# Magnetometers.net
KiCad netlist of a schematic drawn in Altium Designer
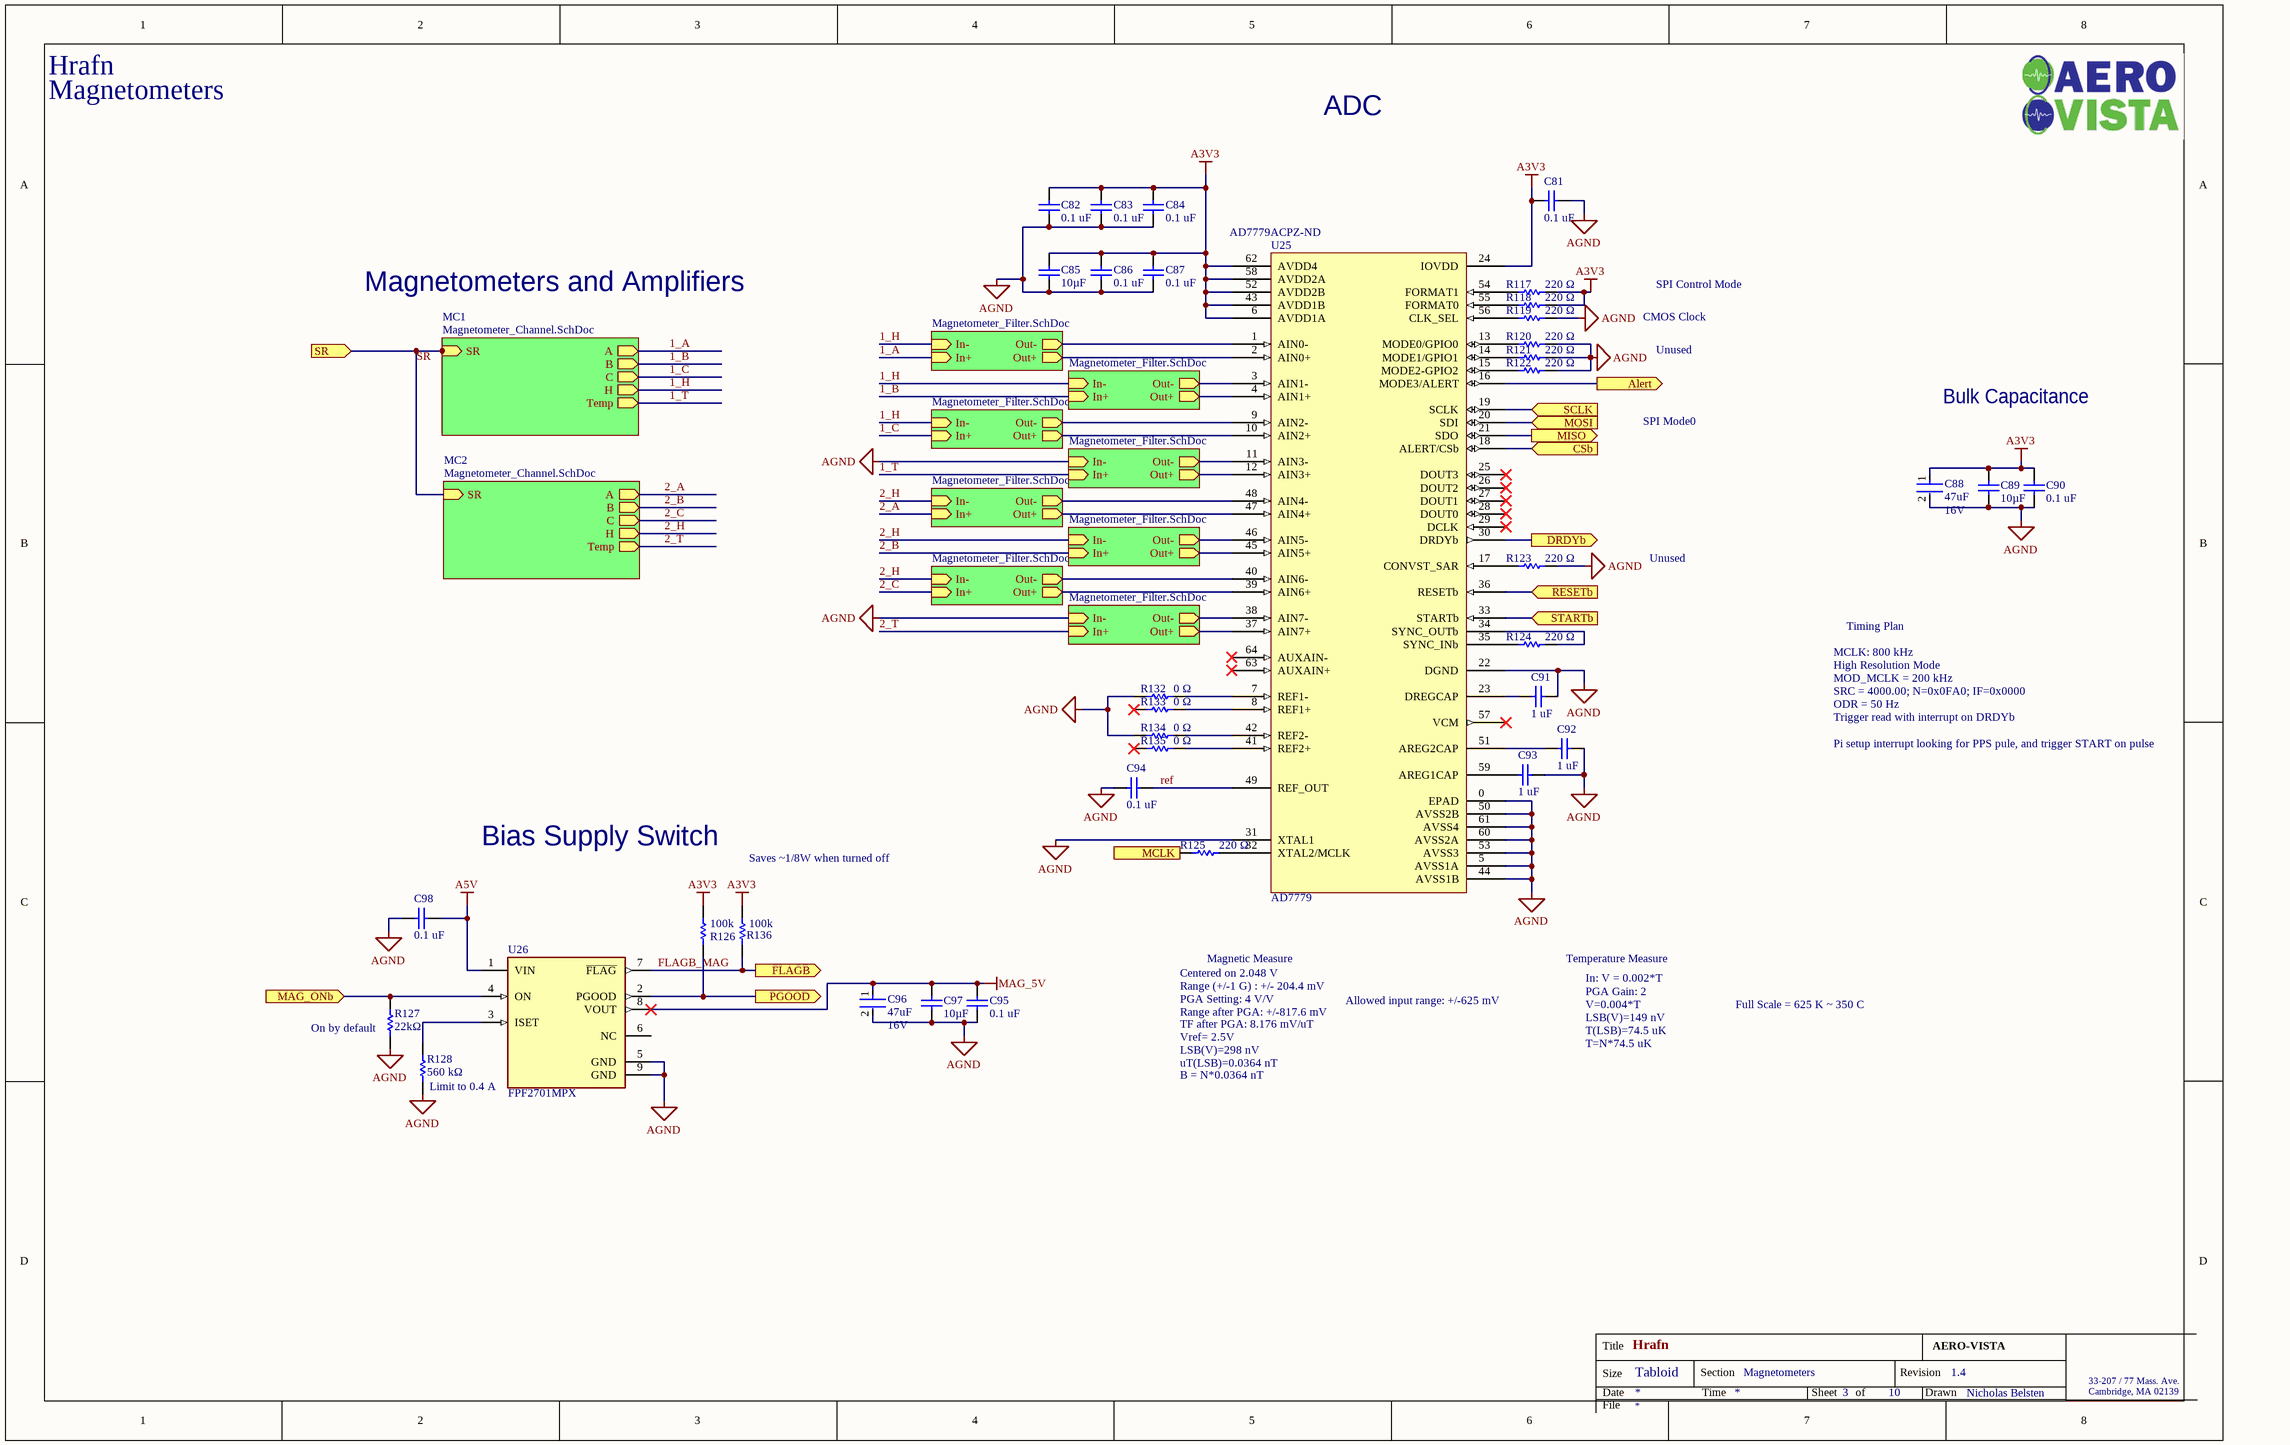
[diagram p0: Magnetometers.SchDoc]

(export (version "E")
  (design (tool "Eeschema 10.0.6"))
  (components
    (comp (ref "C81")
      (value "0.1 uF")
      (footprint "CAPC0402(1005)60_L")
      (description "CAP 100nF 16V ±5% 0402 (1005 Metric) Thickness 0.6mm SMD")
      (fields (field (name "TOLERANCE") "Â±5%"))
      (libsource (lib "Altium Content Vault") (part "CAP"))
    )
    (comp (ref "C82")
      (value "0.1 uF")
      (footprint "CAPC0402(1005)60_L")
      (description "CAP 100nF 16V ±5% 0402 (1005 Metric) Thickness 0.6mm SMD")
      (fields (field (name "TOLERANCE") "Â±5%"))
      (libsource (lib "Altium Content Vault") (part "CAP"))
    )
    (comp (ref "C83")
      (value "0.1 uF")
      (footprint "CAPC0402(1005)60_L")
      (description "CAP 100nF 16V ±5% 0402 (1005 Metric) Thickness 0.6mm SMD")
      (fields (field (name "TOLERANCE") "Â±5%"))
      (libsource (lib "Altium Content Vault") (part "CAP"))
    )
    (comp (ref "C84")
      (value "0.1 uF")
      (footprint "CAPC0402(1005)60_L")
      (description "CAP 100nF 16V ±5% 0402 (1005 Metric) Thickness 0.6mm SMD")
      (fields (field (name "TOLERANCE") "Â±5%"))
      (libsource (lib "Altium Content Vault") (part "CAP"))
    )
    (comp (ref "C85")
      (value "EMK107BBJ106MA-T")
      (footprint "CAPC1608X100X35LL20T25")
      (description "Chip Capacitor, 10 uF, +/- 20%, 16 V, -55 to 85 degC, 0603 (1608 Metric), RoHS, Tape and Reel")
      (fields
        (field (name "CAPACITANCE") "10µF")
        (field (name "MANUFACTURER") "Taiyo Yuden")
        (field (name "TOLERANCE") "±20%")
      )
      (libsource (lib "Altium Content Vault") (part "CAP-NP-2"))
    )
    (comp (ref "C86")
      (value "0.1 uF")
      (footprint "CAPC0402(1005)60_L")
      (description "CAP 100nF 16V ±5% 0402 (1005 Metric) Thickness 0.6mm SMD")
      (fields (field (name "TOLERANCE") "Â±5%"))
      (libsource (lib "Altium Content Vault") (part "CAP"))
    )
    (comp (ref "C87")
      (value "0.1 uF")
      (footprint "CAPC0402(1005)60_L")
      (description "CAP 100nF 16V ±5% 0402 (1005 Metric) Thickness 0.6mm SMD")
      (fields (field (name "TOLERANCE") "Â±5%"))
      (libsource (lib "Altium Content Vault") (part "CAP"))
    )
    (comp (ref "C88")
      (value "GRT32EC81C476ME13L")
      (footprint "FP-GRT32E-0_3-IPC_C")
      (description "Multi-Layer Ceramic Capacitor 47uF 16V X6S ±20% 1210 Emboss T/R")
      (fields
        (field (name "CAPACITANCE") "47uF")
        (field (name "VOLTAGE RATING") "16V")
        (field (name "TOLERANCE") "20%")
      )
      (libsource (lib "Altium Content Vault") (part "02cd4be3c70576c341d710602a673aa"))
    )
    (comp (ref "C89")
      (value "EMK107BBJ106MA-T")
      (footprint "CAPC1608X100X35LL20T25")
      (description "Chip Capacitor, 10 uF, +/- 20%, 16 V, -55 to 85 degC, 0603 (1608 Metric), RoHS, Tape and Reel")
      (fields
        (field (name "CAPACITANCE") "10µF")
        (field (name "MANUFACTURER") "Taiyo Yuden")
        (field (name "TOLERANCE") "±20%")
      )
      (libsource (lib "Altium Content Vault") (part "CAP-NP-2"))
    )
    (comp (ref "C90")
      (value "0.1 uF")
      (footprint "CAPC0402(1005)60_L")
      (description "CAP 100nF 16V ±5% 0402 (1005 Metric) Thickness 0.6mm SMD")
      (fields (field (name "TOLERANCE") "Â±5%"))
      (libsource (lib "Altium Content Vault") (part "CAP"))
    )
    (comp (ref "C91")
      (value "1 uF")
      (footprint "CAPC1005X60X30NL05T10")
      (fields (field (name "PART NUMBER") "C0402C105M8PACTU") (field (name "MANUFACTURER") "Kemet"))
      (libsource (lib "Altium Content Vault") (part "CAP"))
    )
    (comp (ref "C92")
      (value "1 uF")
      (footprint "CAPC1005X60X30NL05T10")
      (fields (field (name "PART NUMBER") "C0402C105M8PACTU") (field (name "MANUFACTURER") "Kemet"))
      (libsource (lib "Altium Content Vault") (part "CAP"))
    )
    (comp (ref "C93")
      (value "1 uF")
      (footprint "CAPC1005X60X30NL05T10")
      (fields (field (name "PART NUMBER") "C0402C105M8PACTU") (field (name "MANUFACTURER") "Kemet"))
      (libsource (lib "Altium Content Vault") (part "CAP"))
    )
    (comp (ref "C94")
      (value "0.1 uF")
      (footprint "CAPC0402(1005)60_L")
      (description "CAP 100nF 16V ±5% 0402 (1005 Metric) Thickness 0.6mm SMD")
      (fields (field (name "TOLERANCE") "Â±5%"))
      (libsource (lib "Altium Content Vault") (part "CAP"))
    )
    (comp (ref "C95")
      (value "0.1 uF")
      (footprint "CAPC0402(1005)60_L")
      (description "CAP 100nF 16V ±5% 0402 (1005 Metric) Thickness 0.6mm SMD")
      (fields (field (name "TOLERANCE") "Â±5%"))
      (libsource (lib "Altium Content Vault") (part "CAP"))
    )
    (comp (ref "C96")
      (value "GRT32EC81C476ME13L")
      (footprint "FP-GRT32E-0_3-IPC_C")
      (description "Multi-Layer Ceramic Capacitor 47uF 16V X6S ±20% 1210 Emboss T/R")
      (fields
        (field (name "CAPACITANCE") "47uF")
        (field (name "VOLTAGE RATING") "16V")
        (field (name "TOLERANCE") "20%")
      )
      (libsource (lib "Altium Content Vault") (part "02cd4be3c70576c341d710602a673aa"))
    )
    (comp (ref "C97")
      (value "EMK107BBJ106MA-T")
      (footprint "CAPC1608X100X35LL20T25")
      (description "Chip Capacitor, 10 uF, +/- 20%, 16 V, -55 to 85 degC, 0603 (1608 Metric), RoHS, Tape and Reel")
      (fields
        (field (name "CAPACITANCE") "10µF")
        (field (name "MANUFACTURER") "Taiyo Yuden")
        (field (name "TOLERANCE") "±20%")
      )
      (libsource (lib "Altium Content Vault") (part "CAP-NP-2"))
    )
    (comp (ref "C98")
      (value "0.1 uF")
      (footprint "CAPC0402(1005)60_L")
      (description "CAP 100nF 16V ±5% 0402 (1005 Metric) Thickness 0.6mm SMD")
      (fields (field (name "TOLERANCE") "Â±5%"))
      (libsource (lib "Altium Content Vault") (part "CAP"))
    )
    (comp (ref "R117")
      (value "220 Ω")
      (footprint "RESC1005X40X25LL05T05")
      (fields (field (name "PART NUMBER") "CRCW040220K0FKED") (field (name "MANUFACTURER") "Vishay Dale"))
      (libsource (lib "Altium Content Vault") (part "RES"))
    )
    (comp (ref "R118")
      (value "220 Ω")
      (footprint "RESC1005X40X25LL05T05")
      (fields (field (name "PART NUMBER") "CRCW040220K0FKED") (field (name "MANUFACTURER") "Vishay Dale"))
      (libsource (lib "Altium Content Vault") (part "RES"))
    )
    (comp (ref "R119")
      (value "220 Ω")
      (footprint "RESC1005X40X25LL05T05")
      (fields (field (name "PART NUMBER") "CRCW040220K0FKED") (field (name "MANUFACTURER") "Vishay Dale"))
      (libsource (lib "Altium Content Vault") (part "RES"))
    )
    (comp (ref "R120")
      (value "220 Ω")
      (footprint "RESC1005X40X25LL05T05")
      (fields (field (name "PART NUMBER") "CRCW040220K0FKED") (field (name "MANUFACTURER") "Vishay Dale"))
      (libsource (lib "Altium Content Vault") (part "RES"))
    )
    (comp (ref "R121")
      (value "220 Ω")
      (footprint "RESC1005X40X25LL05T05")
      (fields (field (name "PART NUMBER") "CRCW040220K0FKED") (field (name "MANUFACTURER") "Vishay Dale"))
      (libsource (lib "Altium Content Vault") (part "RES"))
    )
    (comp (ref "R122")
      (value "220 Ω")
      (footprint "RESC1005X40X25LL05T05")
      (fields (field (name "PART NUMBER") "CRCW040220K0FKED") (field (name "MANUFACTURER") "Vishay Dale"))
      (libsource (lib "Altium Content Vault") (part "RES"))
    )
    (comp (ref "R123")
      (value "220 Ω")
      (footprint "RESC1005X40X25NL05T05")
      (fields (field (name "PART NUMBER") "CRCW040220K0FKED") (field (name "MANUFACTURER") "Vishay Dale"))
      (libsource (lib "Altium Content Vault") (part "RES"))
    )
    (comp (ref "R124")
      (value "220 Ω")
      (footprint "RESC1005X40X25NL05T05")
      (fields (field (name "PART NUMBER") "CRCW040220K0FKED") (field (name "MANUFACTURER") "Vishay Dale"))
      (libsource (lib "Altium Content Vault") (part "RES"))
    )
    (comp (ref "R125")
      (value "220 Ω")
      (footprint "RESC1005X40X25LL05T05")
      (fields (field (name "PART NUMBER") "CRCW040220K0FKED") (field (name "MANUFACTURER") "Vishay Dale"))
      (libsource (lib "Altium Content Vault") (part "RES"))
    )
    (comp (ref "R126")
      (value "CRCW0402100KJNED")
      (footprint "RESC1005X40X25LL05T05")
      (fields (field (name "MANUFACTURER") "Vishay Dale") (field (name "RESISTANCE") "100k"))
      (libsource (lib "Altium Content Vault") (part "RES"))
    )
    (comp (ref "R127")
      (value "22kΩ")
      (footprint "RESC1005X40X25LL05T05")
      (fields (field (name "MANUFACTURER") "Panasonic") (field (name "PART NUMBER") "ERJ-2GEJ223X"))
      (libsource (lib "Altium Content Vault") (part "RES"))
    )
    (comp (ref "R128")
      (value "ERJ2RKF5603X")
      (footprint "RESC1005X40X25LL05T05")
      (fields (field (name "MANUFACTURER") "Panasonic") (field (name "RESISTANCE") "560 kΩ"))
      (libsource (lib "Altium Content Vault") (part "RES"))
    )
    (comp (ref "R132")
      (value "ERJ2GE0R00X")
      (footprint "RESC1005X40X25LL05T05")
      (description "Chip Resistor, 0 Ohm, 0.1 W, -55 to 155 degC, 0402 (1005 Metric), RoHS, Tape and Reel")
      (fields
        (field (name "MANUFACTURER") "Panasonic")
        (field (name "RESISTANCE") "0 Ω")
        (field (name "TOLERANCE") "5%")
      )
      (libsource (lib "Altium Content Vault") (part "RES-2"))
    )
    (comp (ref "R133")
      (value "ERJ2GE0R00X")
      (footprint "RESC1005X40X25LL05T05")
      (description "Chip Resistor, 0 Ohm, 0.1 W, -55 to 155 degC, 0402 (1005 Metric), RoHS, Tape and Reel")
      (fields
        (field (name "MANUFACTURER") "Panasonic")
        (field (name "RESISTANCE") "0 Ω")
        (field (name "TOLERANCE") "5%")
      )
      (libsource (lib "Altium Content Vault") (part "RES-2"))
    )
    (comp (ref "R134")
      (value "ERJ2GE0R00X")
      (footprint "RESC1005X40X25LL05T05")
      (description "Chip Resistor, 0 Ohm, 0.1 W, -55 to 155 degC, 0402 (1005 Metric), RoHS, Tape and Reel")
      (fields
        (field (name "MANUFACTURER") "Panasonic")
        (field (name "RESISTANCE") "0 Ω")
        (field (name "TOLERANCE") "5%")
      )
      (libsource (lib "Altium Content Vault") (part "RES-2"))
    )
    (comp (ref "R135")
      (value "ERJ2GE0R00X")
      (footprint "RESC1005X40X25LL05T05")
      (description "Chip Resistor, 0 Ohm, 0.1 W, -55 to 155 degC, 0402 (1005 Metric), RoHS, Tape and Reel")
      (fields
        (field (name "MANUFACTURER") "Panasonic")
        (field (name "RESISTANCE") "0 Ω")
        (field (name "TOLERANCE") "5%")
      )
      (libsource (lib "Altium Content Vault") (part "RES-2"))
    )
    (comp (ref "R136")
      (value "CRCW0402100KJNED")
      (footprint "RESC1005X40X25LL05T05")
      (fields (field (name "MANUFACTURER") "Vishay Dale") (field (name "RESISTANCE") "100k"))
      (libsource (lib "Altium Content Vault") (part "RES"))
    )
    (comp (ref "U25")
      (value "AD7779")
      (footprint "AD7779")
      (fields (field (name "SUPPLIER PART NUMBER 1") "AD7779ACPZ-ND"))
      (libsource (lib "Hrafn") (part "AD7779"))
    )
    (comp (ref "U26")
      (value "FPF2701MPX")
      (footprint "FP-511DD-MFG")
      (description "IC LOAD SWITCH 0.4-2A OCP 8MLP")
      (fields
        (field (name "OCTOPART") "https://octopart.com/fpf2701mpx-on+semiconductor-84327806")
        (field (name "MANUFACTURER") "ON Semiconductor")
      )
      (libsource (lib "Altium Content Vault") (part "acfcf82852ac67abfbd9dd99c9ad2d6"))
    )
  )
  (nets
    (net (code "11") (name "/Alert") (class "Default")
      (node (ref "U25") (pin "16") (pinfunction "MODE3/ALERT_16") (pintype "bidirectional"))
    )
    (net (code "12") (name "/CSb") (class "Default")
      (node (ref "U25") (pin "18") (pinfunction "ALERT/CSb_18") (pintype "bidirectional"))
    )
    (net (code "13") (name "/DRDYb") (class "Default")
      (node (ref "U25") (pin "30") (pinfunction "DRDYb_30") (pintype "output"))
    )
    (net (code "14") (name "/FLAGB_MAG") (class "Default")
      (node (ref "R136") (pin "1") (pinfunction "1_1") (pintype "passive"))
      (node (ref "U26") (pin "7") (pinfunction "~{FLAG}_7") (pintype "output"))
    )
    (net (code "15") (name "/MAG_ONb") (class "Default")
      (node (ref "R127") (pin "2") (pinfunction "2_2") (pintype "passive"))
      (node (ref "U26") (pin "4") (pinfunction "ON_4") (pintype "input"))
    )
    (net (code "16") (name "/MCLK") (class "Default")
      (node (ref "R125") (pin "1") (pinfunction "1_1") (pintype "passive"))
    )
    (net (code "17") (name "/MISO") (class "Default")
      (node (ref "U25") (pin "21") (pinfunction "SDO_21") (pintype "bidirectional"))
    )
    (net (code "18") (name "/MOSI") (class "Default")
      (node (ref "U25") (pin "20") (pinfunction "SDI_20") (pintype "bidirectional"))
    )
    (net (code "19") (name "/Out+") (class "Default")
      (node (ref "U25") (pin "37") (pinfunction "AIN7+_37") (pintype "input"))
    )
    (net (code "20") (name "/Out+_1") (class "Default")
      (node (ref "U25") (pin "4") (pinfunction "AIN1+_4") (pintype "input"))
    )
    (net (code "21") (name "/Out+_2") (class "Default")
      (node (ref "U25") (pin "2") (pinfunction "AIN0+_2") (pintype "input"))
    )
    (net (code "22") (name "/Out+_3") (class "Default")
      (node (ref "U25") (pin "10") (pinfunction "AIN2+_10") (pintype "input"))
    )
    (net (code "23") (name "/Out+_4") (class "Default")
      (node (ref "U25") (pin "47") (pinfunction "AIN4+_47") (pintype "input"))
    )
    (net (code "24") (name "/Out+_5") (class "Default")
      (node (ref "U25") (pin "12") (pinfunction "AIN3+_12") (pintype "input"))
    )
    (net (code "25") (name "/Out+_6") (class "Default")
      (node (ref "U25") (pin "39") (pinfunction "AIN6+_39") (pintype "input"))
    )
    (net (code "26") (name "/Out+_7") (class "Default")
      (node (ref "U25") (pin "45") (pinfunction "AIN5+_45") (pintype "input"))
    )
    (net (code "27") (name "/Out-") (class "Default")
      (node (ref "U25") (pin "38") (pinfunction "AIN7-_38") (pintype "input"))
    )
    (net (code "28") (name "/Out-_1") (class "Default")
      (node (ref "U25") (pin "1") (pinfunction "AIN0-_1") (pintype "input"))
    )
    (net (code "29") (name "/Out-_2") (class "Default")
      (node (ref "U25") (pin "3") (pinfunction "AIN1-_3") (pintype "input"))
    )
    (net (code "30") (name "/Out-_3") (class "Default")
      (node (ref "U25") (pin "9") (pinfunction "AIN2-_9") (pintype "input"))
    )
    (net (code "31") (name "/Out-_4") (class "Default")
      (node (ref "U25") (pin "48") (pinfunction "AIN4-_48") (pintype "input"))
    )
    (net (code "32") (name "/Out-_5") (class "Default")
      (node (ref "U25") (pin "11") (pinfunction "AIN3-_11") (pintype "input"))
    )
    (net (code "33") (name "/Out-_6") (class "Default")
      (node (ref "U25") (pin "46") (pinfunction "AIN5-_46") (pintype "input"))
    )
    (net (code "34") (name "/Out-_7") (class "Default")
      (node (ref "U25") (pin "40") (pinfunction "AIN6-_40") (pintype "input"))
    )
    (net (code "35") (name "/PGOOD") (class "Default")
      (node (ref "R126") (pin "1") (pinfunction "1_1") (pintype "passive"))
      (node (ref "U26") (pin "2") (pinfunction "PGOOD_2") (pintype "output"))
    )
    (net (code "36") (name "/RESETb") (class "Default")
      (node (ref "U25") (pin "36") (pinfunction "RESETb_36") (pintype "input"))
    )
    (net (code "37") (name "/SCLK") (class "Default")
      (node (ref "U25") (pin "19") (pinfunction "SCLK_19") (pintype "bidirectional"))
    )
    (net (code "39") (name "/STARTb") (class "Default")
      (node (ref "U25") (pin "33") (pinfunction "STARTb_33") (pintype "input"))
    )
    (net (code "40") (name "/ref") (class "Default")
      (node (ref "C94") (pin "2") (pinfunction "2_2") (pintype "passive"))
      (node (ref "U25") (pin "49") (pinfunction "REF_OUT_49") (pintype "passive"))
    )
    (net (code "41") (name "A3V3") (class "Default")
      (node (ref "C81") (pin "2") (pinfunction "2_2") (pintype "passive"))
      (node (ref "C82") (pin "2") (pinfunction "2_2") (pintype "passive"))
      (node (ref "C83") (pin "2") (pinfunction "2_2") (pintype "passive"))
      (node (ref "C84") (pin "2") (pinfunction "2_2") (pintype "passive"))
      (node (ref "C85") (pin "2") (pinfunction "2_2") (pintype "passive"))
      (node (ref "C86") (pin "2") (pinfunction "2_2") (pintype "passive"))
      (node (ref "C87") (pin "2") (pinfunction "2_2") (pintype "passive"))
      (node (ref "C88") (pin "1") (pinfunction "1_1") (pintype "passive"))
      (node (ref "C89") (pin "2") (pinfunction "2_2") (pintype "passive"))
      (node (ref "C90") (pin "2") (pinfunction "2_2") (pintype "passive"))
      (node (ref "R117") (pin "2") (pinfunction "2_2") (pintype "passive"))
      (node (ref "R118") (pin "2") (pinfunction "2_2") (pintype "passive"))
      (node (ref "R126") (pin "2") (pinfunction "2_2") (pintype "passive"))
      (node (ref "R136") (pin "2") (pinfunction "2_2") (pintype "passive"))
      (node (ref "U25") (pin "24") (pinfunction "IOVDD_24") (pintype "power_in"))
      (node (ref "U25") (pin "43") (pinfunction "AVDD1B_43") (pintype "power_in"))
      (node (ref "U25") (pin "52") (pinfunction "AVDD2B_52") (pintype "power_in"))
      (node (ref "U25") (pin "58") (pinfunction "AVDD2A_58") (pintype "power_in"))
      (node (ref "U25") (pin "6") (pinfunction "AVDD1A_6") (pintype "power_in"))
      (node (ref "U25") (pin "62") (pinfunction "AVDD4_62") (pintype "power_in"))
    )
    (net (code "42") (name "A5V") (class "Default")
      (node (ref "C98") (pin "2") (pinfunction "2_2") (pintype "passive"))
      (node (ref "U26") (pin "1") (pinfunction "VIN_1") (pintype "power_in"))
    )
    (net (code "43") (name "AGND") (class "Default")
      (node (ref "C81") (pin "1") (pinfunction "1_1") (pintype "passive"))
      (node (ref "C82") (pin "1") (pinfunction "1_1") (pintype "passive"))
      (node (ref "C83") (pin "1") (pinfunction "1_1") (pintype "passive"))
      (node (ref "C84") (pin "1") (pinfunction "1_1") (pintype "passive"))
      (node (ref "C85") (pin "1") (pinfunction "1_1") (pintype "passive"))
      (node (ref "C86") (pin "1") (pinfunction "1_1") (pintype "passive"))
      (node (ref "C87") (pin "1") (pinfunction "1_1") (pintype "passive"))
      (node (ref "C88") (pin "2") (pinfunction "2_2") (pintype "passive"))
      (node (ref "C89") (pin "1") (pinfunction "1_1") (pintype "passive"))
      (node (ref "C90") (pin "1") (pinfunction "1_1") (pintype "passive"))
      (node (ref "C91") (pin "1") (pinfunction "1_1") (pintype "passive"))
      (node (ref "C92") (pin "1") (pinfunction "1_1") (pintype "passive"))
      (node (ref "C93") (pin "1") (pinfunction "1_1") (pintype "passive"))
      (node (ref "C94") (pin "1") (pinfunction "1_1") (pintype "passive"))
      (node (ref "C95") (pin "1") (pinfunction "1_1") (pintype "passive"))
      (node (ref "C96") (pin "2") (pinfunction "2_2") (pintype "passive"))
      (node (ref "C97") (pin "1") (pinfunction "1_1") (pintype "passive"))
      (node (ref "C98") (pin "1") (pinfunction "1_1") (pintype "passive"))
      (node (ref "R119") (pin "2") (pinfunction "2_2") (pintype "passive"))
      (node (ref "R120") (pin "2") (pinfunction "2_2") (pintype "passive"))
      (node (ref "R121") (pin "2") (pinfunction "2_2") (pintype "passive"))
      (node (ref "R122") (pin "2") (pinfunction "2_2") (pintype "passive"))
      (node (ref "R123") (pin "2") (pinfunction "2_2") (pintype "passive"))
      (node (ref "R127") (pin "1") (pinfunction "1_1") (pintype "passive"))
      (node (ref "R128") (pin "1") (pinfunction "1_1") (pintype "passive"))
      (node (ref "R132") (pin "1") (pinfunction "1_1") (pintype "passive"))
      (node (ref "R134") (pin "1") (pinfunction "1_1") (pintype "passive"))
      (node (ref "U25") (pin "0") (pinfunction "EPAD_0") (pintype "power_in"))
      (node (ref "U25") (pin "22") (pinfunction "DGND_22") (pintype "power_in"))
      (node (ref "U25") (pin "31") (pinfunction "XTAL1_31") (pintype "passive"))
      (node (ref "U25") (pin "44") (pinfunction "AVSS1B_44") (pintype "power_in"))
      (node (ref "U25") (pin "5") (pinfunction "AVSS1A_5") (pintype "power_in"))
      (node (ref "U25") (pin "50") (pinfunction "AVSS2B_50") (pintype "power_in"))
      (node (ref "U25") (pin "53") (pinfunction "AVSS3_53") (pintype "power_in"))
      (node (ref "U25") (pin "60") (pinfunction "AVSS2A_60") (pintype "power_in"))
      (node (ref "U25") (pin "61") (pinfunction "AVSS4_61") (pintype "power_in"))
      (node (ref "U26") (pin "5") (pinfunction "GND_5") (pintype "power_in"))
      (node (ref "U26") (pin "9") (pinfunction "GND_9") (pintype "power_in"))
    )
    (net (code "44") (name "MAG_5V") (class "Default")
      (node (ref "C95") (pin "2") (pinfunction "2_2") (pintype "passive"))
      (node (ref "C96") (pin "1") (pinfunction "1_1") (pintype "passive"))
      (node (ref "C97") (pin "2") (pinfunction "2_2") (pintype "passive"))
      (node (ref "U26") (pin "8") (pinfunction "VOUT_8") (pintype "output"))
    )
    (net (code "45") (name "Net-(U25-AREG1CAP)") (class "Default")
      (node (ref "C93") (pin "2") (pinfunction "2_2") (pintype "passive"))
      (node (ref "U25") (pin "59") (pinfunction "AREG1CAP_59") (pintype "passive"))
    )
    (net (code "46") (name "Net-(U25-AREG2CAP)") (class "Default")
      (node (ref "C92") (pin "2") (pinfunction "2_2") (pintype "passive"))
      (node (ref "U25") (pin "51") (pinfunction "AREG2CAP_51") (pintype "passive"))
    )
    (net (code "47") (name "Net-(U25-CLK_SEL)") (class "Default")
      (node (ref "R119") (pin "1") (pinfunction "1_1") (pintype "passive"))
      (node (ref "U25") (pin "56") (pinfunction "CLK_SEL_56") (pintype "input"))
    )
    (net (code "48") (name "Net-(U25-CONVST_SAR)") (class "Default")
      (node (ref "R123") (pin "1") (pinfunction "1_1") (pintype "passive"))
      (node (ref "U25") (pin "17") (pinfunction "CONVST_SAR_17") (pintype "input"))
    )
    (net (code "49") (name "Net-(U25-DREGCAP)") (class "Default")
      (node (ref "C91") (pin "2") (pinfunction "2_2") (pintype "passive"))
      (node (ref "U25") (pin "23") (pinfunction "DREGCAP_23") (pintype "passive"))
    )
    (net (code "50") (name "Net-(U25-FORMAT0)") (class "Default")
      (node (ref "R118") (pin "1") (pinfunction "1_1") (pintype "passive"))
      (node (ref "U25") (pin "55") (pinfunction "FORMAT0_55") (pintype "input"))
    )
    (net (code "51") (name "Net-(U25-FORMAT1)") (class "Default")
      (node (ref "R117") (pin "1") (pinfunction "1_1") (pintype "passive"))
      (node (ref "U25") (pin "54") (pinfunction "FORMAT1_54") (pintype "input"))
    )
    (net (code "52") (name "Net-(U25-MODE0{slash}GPIO0)") (class "Default")
      (node (ref "R120") (pin "1") (pinfunction "1_1") (pintype "passive"))
      (node (ref "U25") (pin "13") (pinfunction "MODE0/GPIO0_13") (pintype "bidirectional"))
    )
    (net (code "53") (name "Net-(U25-MODE1{slash}GPIO1)") (class "Default")
      (node (ref "R121") (pin "1") (pinfunction "1_1") (pintype "passive"))
      (node (ref "U25") (pin "14") (pinfunction "MODE1/GPIO1_14") (pintype "bidirectional"))
    )
    (net (code "54") (name "Net-(U25-MODE2-GPIO2)") (class "Default")
      (node (ref "R122") (pin "1") (pinfunction "1_1") (pintype "passive"))
      (node (ref "U25") (pin "15") (pinfunction "MODE2-GPIO2_15") (pintype "bidirectional"))
    )
    (net (code "55") (name "Net-(U25-REF1+)") (class "Default")
      (node (ref "R133") (pin "2") (pinfunction "2_2") (pintype "passive"))
      (node (ref "U25") (pin "8") (pinfunction "REF1+_8") (pintype "input"))
    )
    (net (code "56") (name "Net-(U25-REF1-)") (class "Default")
      (node (ref "R132") (pin "2") (pinfunction "2_2") (pintype "passive"))
      (node (ref "U25") (pin "7") (pinfunction "REF1-_7") (pintype "input"))
    )
    (net (code "57") (name "Net-(U25-REF2+)") (class "Default")
      (node (ref "R135") (pin "2") (pinfunction "2_2") (pintype "passive"))
      (node (ref "U25") (pin "41") (pinfunction "REF2+_41") (pintype "input"))
    )
    (net (code "58") (name "Net-(U25-REF2-)") (class "Default")
      (node (ref "R134") (pin "2") (pinfunction "2_2") (pintype "passive"))
      (node (ref "U25") (pin "42") (pinfunction "REF2-_42") (pintype "input"))
    )
    (net (code "59") (name "Net-(U25-SYNC_INb)") (class "Default")
      (node (ref "R124") (pin "1") (pinfunction "1_1") (pintype "passive"))
      (node (ref "U25") (pin "35") (pinfunction "SYNC_INb_35") (pintype "passive"))
    )
    (net (code "60") (name "Net-(U25-SYNC_OUTb)") (class "Default")
      (node (ref "R124") (pin "2") (pinfunction "2_2") (pintype "passive"))
      (node (ref "U25") (pin "34") (pinfunction "SYNC_OUTb_34") (pintype "passive"))
    )
    (net (code "61") (name "Net-(U25-XTAL2{slash}MCLK)") (class "Default")
      (node (ref "R125") (pin "2") (pinfunction "2_2") (pintype "passive"))
      (node (ref "U25") (pin "32") (pinfunction "XTAL2/MCLK_32") (pintype "passive"))
    )
    (net (code "62") (name "Net-(U26-ISET)") (class "Default")
      (node (ref "R128") (pin "2") (pinfunction "2_2") (pintype "passive"))
      (node (ref "U26") (pin "3") (pinfunction "ISET_3") (pintype "input"))
    )
    (net (code "63") (name "unconnected-(R133-Pad1)") (class "Default")
      (node (ref "R133") (pin "1") (pinfunction "1_1") (pintype "passive+no_connect"))
    )
    (net (code "64") (name "unconnected-(R135-Pad1)") (class "Default")
      (node (ref "R135") (pin "1") (pinfunction "1_1") (pintype "passive+no_connect"))
    )
    (net (code "65") (name "unconnected-(U25-AUXAIN+-Pad63)") (class "Default")
      (node (ref "U25") (pin "63") (pinfunction "AUXAIN+_63") (pintype "input+no_connect"))
    )
    (net (code "66") (name "unconnected-(U25-AUXAIN--Pad64)") (class "Default")
      (node (ref "U25") (pin "64") (pinfunction "AUXAIN-_64") (pintype "input+no_connect"))
    )
    (net (code "67") (name "unconnected-(U25-DCLK-Pad29)") (class "Default")
      (node (ref "U25") (pin "29") (pinfunction "DCLK_29") (pintype "input+no_connect"))
    )
    (net (code "68") (name "unconnected-(U25-DOUT0-Pad28)") (class "Default")
      (node (ref "U25") (pin "28") (pinfunction "DOUT0_28") (pintype "bidirectional+no_connect"))
    )
    (net (code "69") (name "unconnected-(U25-DOUT1-Pad27)") (class "Default")
      (node (ref "U25") (pin "27") (pinfunction "DOUT1_27") (pintype "bidirectional+no_connect"))
    )
    (net (code "70") (name "unconnected-(U25-DOUT2-Pad26)") (class "Default")
      (node (ref "U25") (pin "26") (pinfunction "DOUT2_26") (pintype "bidirectional+no_connect"))
    )
    (net (code "71") (name "unconnected-(U25-DOUT3-Pad25)") (class "Default")
      (node (ref "U25") (pin "25") (pinfunction "DOUT3_25") (pintype "bidirectional+no_connect"))
    )
    (net (code "72") (name "unconnected-(U25-VCM-Pad57)") (class "Default")
      (node (ref "U25") (pin "57") (pinfunction "VCM_57") (pintype "output+no_connect"))
    )
    (net (code "73") (name "unconnected-(U26-NC-Pad6)") (class "Default")
      (node (ref "U26") (pin "6") (pinfunction "NC_6") (pintype "passive"))
    )
  )
)
